# binaryClock.net
KiCad netlist of a schematic drawn in EAGLE
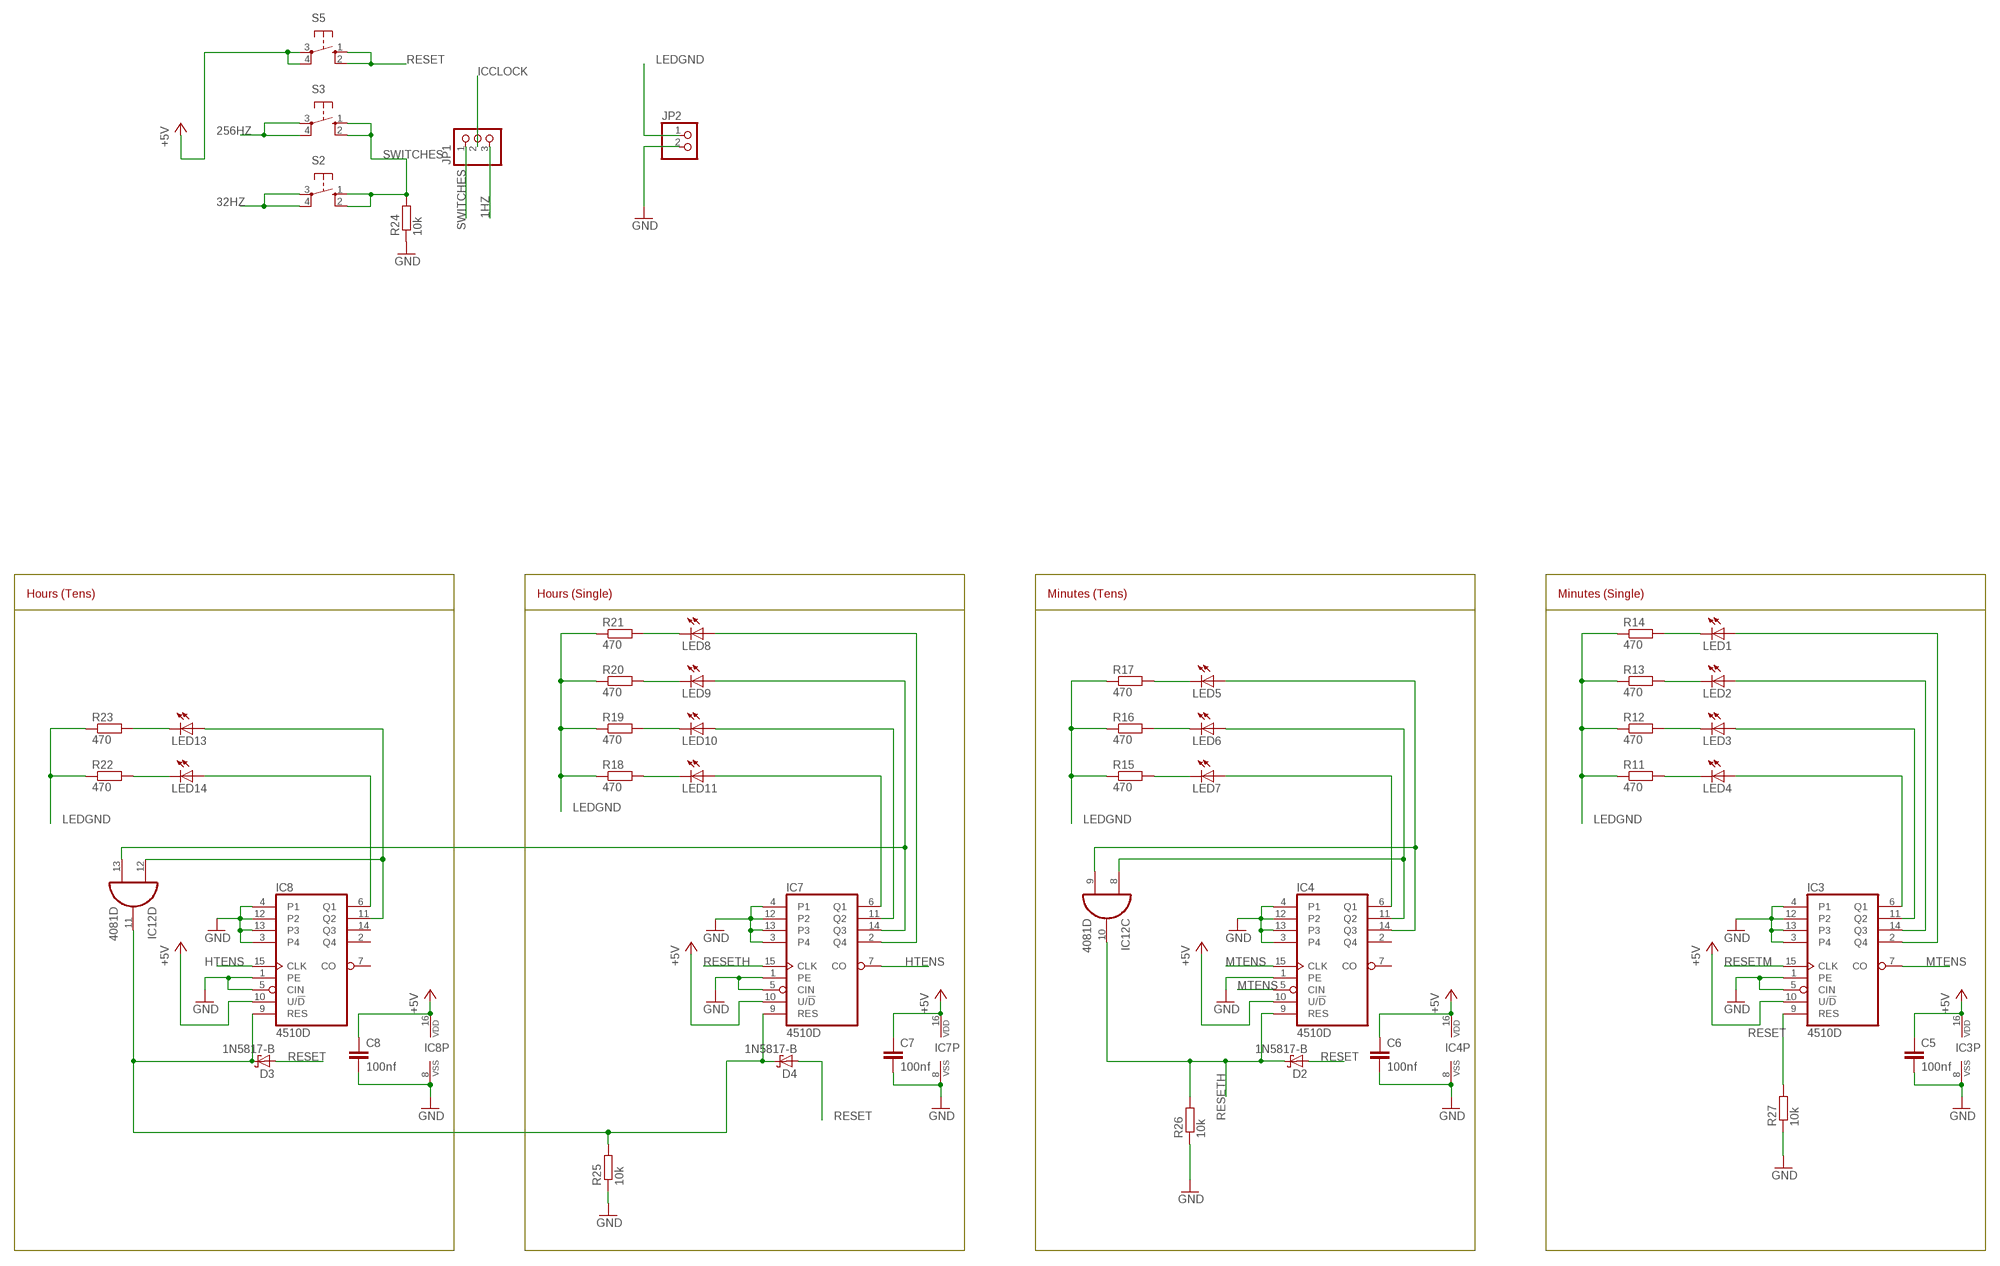
[diagram p0: schematic, sheet 1, part 1 of 2]
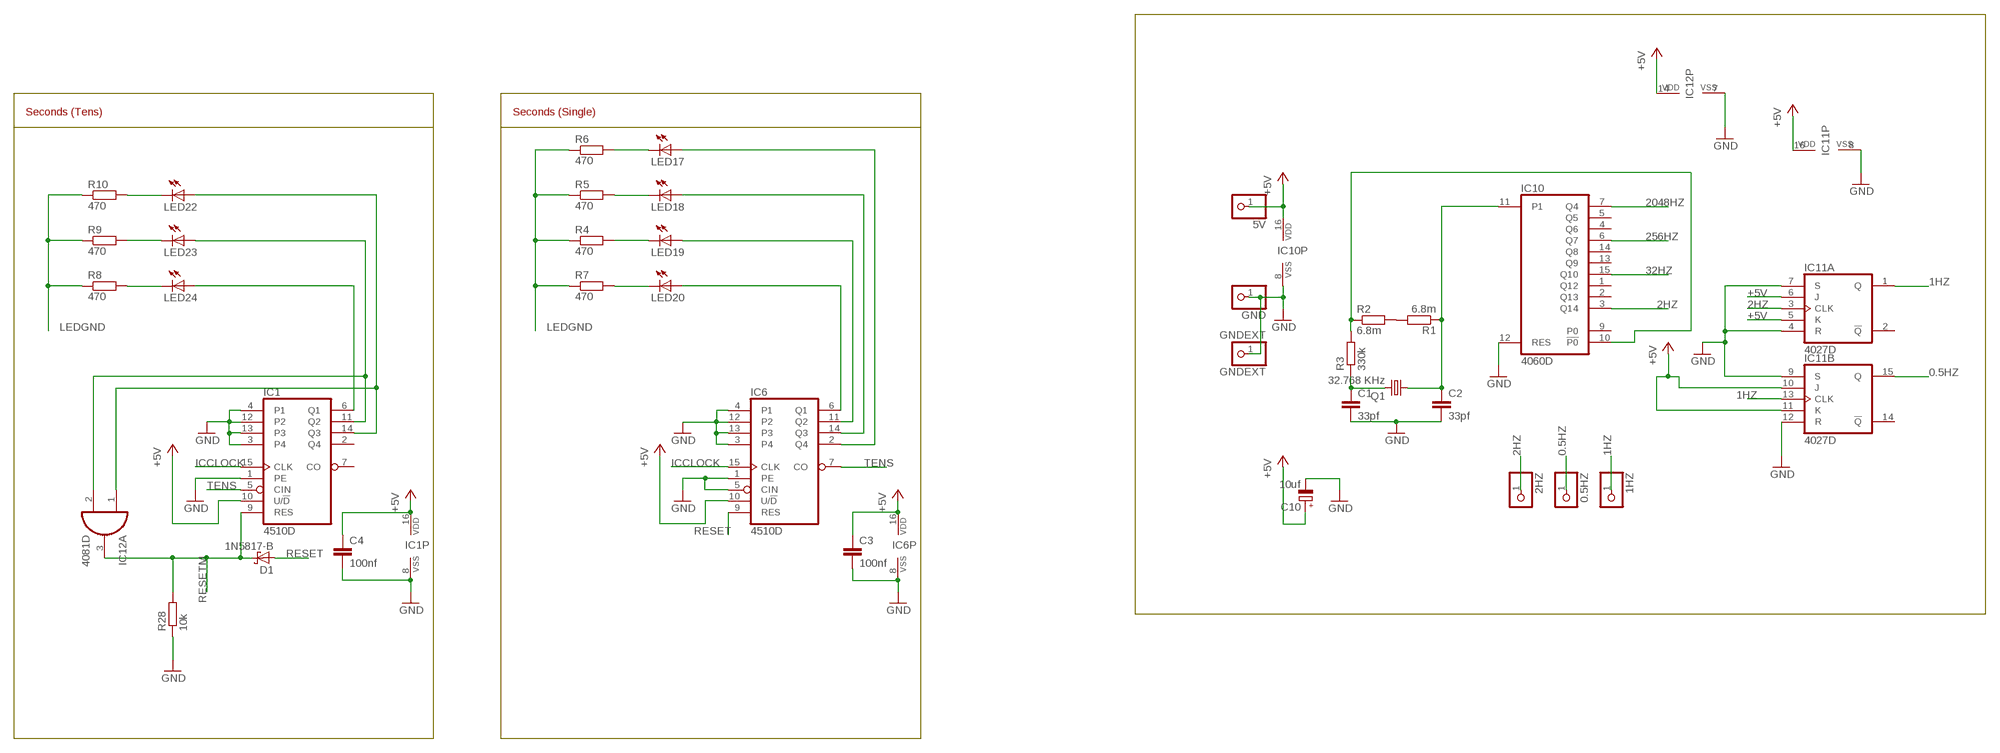
[diagram p1: schematic, sheet 1, part 2 of 2]

(export (version "E")
  (design (tool "Eeschema 10.0.6"))
  (components
    (comp (ref "0.5HZ")
      (value "PINHD-1X1")
      (footprint "eagle-import:1X01")
      (libsource (lib "eagle-import") (part "PINHD-1X1"))
    )
    (comp (ref "1HZ")
      (value "PINHD-1X1")
      (footprint "eagle-import:1X01")
      (libsource (lib "eagle-import") (part "PINHD-1X1"))
    )
    (comp (ref "2HZ")
      (value "PINHD-1X1")
      (footprint "eagle-import:1X01")
      (libsource (lib "eagle-import") (part "PINHD-1X1"))
    )
    (comp (ref "5V")
      (value "PINHD-1X1")
      (footprint "eagle-import:1X01")
      (libsource (lib "eagle-import") (part "PINHD-1X1"))
    )
    (comp (ref "C1")
      (value "33pf")
      (footprint "eagle-import:C025-030X050")
      (libsource (lib "eagle-import") (part "C-EU025-030X050"))
    )
    (comp (ref "C2")
      (value "33pf")
      (footprint "eagle-import:C025-030X050")
      (libsource (lib "eagle-import") (part "C-EU025-030X050"))
    )
    (comp (ref "C3")
      (value "100nf")
      (footprint "eagle-import:C025-030X050")
      (libsource (lib "eagle-import") (part "C-EU025-030X050"))
    )
    (comp (ref "C4")
      (value "100nf")
      (footprint "eagle-import:C025-030X050")
      (libsource (lib "eagle-import") (part "C-EU025-030X050"))
    )
    (comp (ref "C5")
      (value "100nf")
      (footprint "eagle-import:C025-030X050")
      (libsource (lib "eagle-import") (part "C-EU025-030X050"))
    )
    (comp (ref "C6")
      (value "100nf")
      (footprint "eagle-import:C025-030X050")
      (libsource (lib "eagle-import") (part "C-EU025-030X050"))
    )
    (comp (ref "C7")
      (value "100nf")
      (footprint "eagle-import:C025-030X050")
      (libsource (lib "eagle-import") (part "C-EU025-030X050"))
    )
    (comp (ref "C8")
      (value "100nf")
      (footprint "eagle-import:C025-030X050")
      (libsource (lib "eagle-import") (part "C-EU025-030X050"))
    )
    (comp (ref "C10")
      (value "10uf")
      (footprint "eagle-import:E2,5-5")
      (libsource (lib "eagle-import") (part "CPOL-EUE2.5-5"))
    )
    (comp (ref "D1")
      (value "1N5817-B")
      (footprint "eagle-import:DO41-7.6")
      (libsource (lib "eagle-import") (part "1N5817-B"))
    )
    (comp (ref "D2")
      (value "1N5817-B")
      (footprint "eagle-import:DO41-7.6")
      (libsource (lib "eagle-import") (part "1N5817-B"))
    )
    (comp (ref "D3")
      (value "1N5817-B")
      (footprint "eagle-import:DO41-7.6")
      (libsource (lib "eagle-import") (part "1N5817-B"))
    )
    (comp (ref "D4")
      (value "1N5817-B")
      (footprint "eagle-import:DO41-7.6")
      (libsource (lib "eagle-import") (part "1N5817-B"))
    )
    (comp (ref "GND")
      (value "PINHD-1X1")
      (footprint "eagle-import:1X01")
      (libsource (lib "eagle-import") (part "PINHD-1X1"))
    )
    (comp (ref "GNDEXT")
      (value "GNDEXT")
      (footprint "eagle-import:1X01")
      (libsource (lib "eagle-import") (part "PINHD-1X1"))
    )
    (comp (ref "IC1")
      (value "4510D")
      (footprint "eagle-import:SO16")
      (libsource (lib "eagle-import") (part "4510D"))
    )
    (comp (ref "IC3")
      (value "4510D")
      (footprint "eagle-import:SO16")
      (libsource (lib "eagle-import") (part "4510D"))
    )
    (comp (ref "IC4")
      (value "4510D")
      (footprint "eagle-import:SO16")
      (libsource (lib "eagle-import") (part "4510D"))
    )
    (comp (ref "IC6")
      (value "4510D")
      (footprint "eagle-import:SO16")
      (libsource (lib "eagle-import") (part "4510D"))
    )
    (comp (ref "IC7")
      (value "4510D")
      (footprint "eagle-import:SO16")
      (libsource (lib "eagle-import") (part "4510D"))
    )
    (comp (ref "IC8")
      (value "4510D")
      (footprint "eagle-import:SO16")
      (libsource (lib "eagle-import") (part "4510D"))
    )
    (comp (ref "IC10")
      (value "4060D")
      (footprint "eagle-import:SO16")
      (libsource (lib "eagle-import") (part "4060D"))
    )
    (comp (ref "IC11")
      (value "4027D")
      (footprint "eagle-import:SO16")
      (libsource (lib "eagle-import") (part "4027D"))
    )
    (comp (ref "IC12")
      (value "4081D")
      (footprint "eagle-import:SO14")
      (libsource (lib "eagle-import") (part "4081D"))
    )
    (comp (ref "JP1")
      (value "PINHD-1X3")
      (footprint "eagle-import:1X03")
      (libsource (lib "eagle-import") (part "PINHD-1X3"))
    )
    (comp (ref "JP2")
      (value "PINHD-1X2")
      (footprint "eagle-import:1X02")
      (libsource (lib "eagle-import") (part "PINHD-1X2"))
    )
    (comp (ref "LED1")
      (value "LED5MM")
      (footprint "eagle-import:LED5MM")
      (libsource (lib "eagle-import") (part "LED5MM"))
    )
    (comp (ref "LED2")
      (value "LED5MM")
      (footprint "eagle-import:LED5MM")
      (libsource (lib "eagle-import") (part "LED5MM"))
    )
    (comp (ref "LED3")
      (value "LED5MM")
      (footprint "eagle-import:LED5MM")
      (libsource (lib "eagle-import") (part "LED5MM"))
    )
    (comp (ref "LED4")
      (value "LED5MM")
      (footprint "eagle-import:LED5MM")
      (libsource (lib "eagle-import") (part "LED5MM"))
    )
    (comp (ref "LED5")
      (value "LED5MM")
      (footprint "eagle-import:LED5MM")
      (libsource (lib "eagle-import") (part "LED5MM"))
    )
    (comp (ref "LED6")
      (value "LED5MM")
      (footprint "eagle-import:LED5MM")
      (libsource (lib "eagle-import") (part "LED5MM"))
    )
    (comp (ref "LED7")
      (value "LED5MM")
      (footprint "eagle-import:LED5MM")
      (libsource (lib "eagle-import") (part "LED5MM"))
    )
    (comp (ref "LED8")
      (value "LED5MM")
      (footprint "eagle-import:LED5MM")
      (libsource (lib "eagle-import") (part "LED5MM"))
    )
    (comp (ref "LED9")
      (value "LED5MM")
      (footprint "eagle-import:LED5MM")
      (libsource (lib "eagle-import") (part "LED5MM"))
    )
    (comp (ref "LED10")
      (value "LED5MM")
      (footprint "eagle-import:LED5MM")
      (libsource (lib "eagle-import") (part "LED5MM"))
    )
    (comp (ref "LED11")
      (value "LED5MM")
      (footprint "eagle-import:LED5MM")
      (libsource (lib "eagle-import") (part "LED5MM"))
    )
    (comp (ref "LED13")
      (value "LED5MM")
      (footprint "eagle-import:LED5MM")
      (libsource (lib "eagle-import") (part "LED5MM"))
    )
    (comp (ref "LED14")
      (value "LED5MM")
      (footprint "eagle-import:LED5MM")
      (libsource (lib "eagle-import") (part "LED5MM"))
    )
    (comp (ref "LED17")
      (value "LED5MM")
      (footprint "eagle-import:LED5MM")
      (libsource (lib "eagle-import") (part "LED5MM"))
    )
    (comp (ref "LED18")
      (value "LED5MM")
      (footprint "eagle-import:LED5MM")
      (libsource (lib "eagle-import") (part "LED5MM"))
    )
    (comp (ref "LED19")
      (value "LED5MM")
      (footprint "eagle-import:LED5MM")
      (libsource (lib "eagle-import") (part "LED5MM"))
    )
    (comp (ref "LED20")
      (value "LED5MM")
      (footprint "eagle-import:LED5MM")
      (libsource (lib "eagle-import") (part "LED5MM"))
    )
    (comp (ref "LED22")
      (value "LED5MM")
      (footprint "eagle-import:LED5MM")
      (libsource (lib "eagle-import") (part "LED5MM"))
    )
    (comp (ref "LED23")
      (value "LED5MM")
      (footprint "eagle-import:LED5MM")
      (libsource (lib "eagle-import") (part "LED5MM"))
    )
    (comp (ref "LED24")
      (value "LED5MM")
      (footprint "eagle-import:LED5MM")
      (libsource (lib "eagle-import") (part "LED5MM"))
    )
    (comp (ref "Q1")
      (value "32.768 KHz")
      (footprint "eagle-import:TC26H")
      (libsource (lib "eagle-import") (part "CRYSTALTC26H"))
    )
    (comp (ref "R1")
      (value "6.8m")
      (footprint "eagle-import:R0805")
      (libsource (lib "eagle-import") (part "R-EU_R0805"))
    )
    (comp (ref "R2")
      (value "6.8m")
      (footprint "eagle-import:R0805")
      (libsource (lib "eagle-import") (part "R-EU_R0805"))
    )
    (comp (ref "R3")
      (value "330k")
      (footprint "eagle-import:R0805")
      (libsource (lib "eagle-import") (part "R-EU_R0805"))
    )
    (comp (ref "R4")
      (value "470")
      (footprint "eagle-import:R0805")
      (libsource (lib "eagle-import") (part "R-EU_R0805"))
    )
    (comp (ref "R5")
      (value "470")
      (footprint "eagle-import:R0805")
      (libsource (lib "eagle-import") (part "R-EU_R0805"))
    )
    (comp (ref "R6")
      (value "470")
      (footprint "eagle-import:R0805")
      (libsource (lib "eagle-import") (part "R-EU_R0805"))
    )
    (comp (ref "R7")
      (value "470")
      (footprint "eagle-import:R0805")
      (libsource (lib "eagle-import") (part "R-EU_R0805"))
    )
    (comp (ref "R8")
      (value "470")
      (footprint "eagle-import:R0805")
      (libsource (lib "eagle-import") (part "R-EU_R0805"))
    )
    (comp (ref "R9")
      (value "470")
      (footprint "eagle-import:R0805")
      (libsource (lib "eagle-import") (part "R-EU_R0805"))
    )
    (comp (ref "R10")
      (value "470")
      (footprint "eagle-import:R0805")
      (libsource (lib "eagle-import") (part "R-EU_R0805"))
    )
    (comp (ref "R11")
      (value "470")
      (footprint "eagle-import:R0805")
      (libsource (lib "eagle-import") (part "R-EU_R0805"))
    )
    (comp (ref "R12")
      (value "470")
      (footprint "eagle-import:R0805")
      (libsource (lib "eagle-import") (part "R-EU_R0805"))
    )
    (comp (ref "R13")
      (value "470")
      (footprint "eagle-import:R0805")
      (libsource (lib "eagle-import") (part "R-EU_R0805"))
    )
    (comp (ref "R14")
      (value "470")
      (footprint "eagle-import:R0805")
      (libsource (lib "eagle-import") (part "R-EU_R0805"))
    )
    (comp (ref "R15")
      (value "470")
      (footprint "eagle-import:R0805")
      (libsource (lib "eagle-import") (part "R-EU_R0805"))
    )
    (comp (ref "R16")
      (value "470")
      (footprint "eagle-import:R0805")
      (libsource (lib "eagle-import") (part "R-EU_R0805"))
    )
    (comp (ref "R17")
      (value "470")
      (footprint "eagle-import:R0805")
      (libsource (lib "eagle-import") (part "R-EU_R0805"))
    )
    (comp (ref "R18")
      (value "470")
      (footprint "eagle-import:R0805")
      (libsource (lib "eagle-import") (part "R-EU_R0805"))
    )
    (comp (ref "R19")
      (value "470")
      (footprint "eagle-import:R0805")
      (libsource (lib "eagle-import") (part "R-EU_R0805"))
    )
    (comp (ref "R20")
      (value "470")
      (footprint "eagle-import:R0805")
      (libsource (lib "eagle-import") (part "R-EU_R0805"))
    )
    (comp (ref "R21")
      (value "470")
      (footprint "eagle-import:R0805")
      (libsource (lib "eagle-import") (part "R-EU_R0805"))
    )
    (comp (ref "R22")
      (value "470")
      (footprint "eagle-import:R0805")
      (libsource (lib "eagle-import") (part "R-EU_R0805"))
    )
    (comp (ref "R23")
      (value "470")
      (footprint "eagle-import:R0805")
      (libsource (lib "eagle-import") (part "R-EU_R0805"))
    )
    (comp (ref "R24")
      (value "10k")
      (footprint "eagle-import:R0805")
      (libsource (lib "eagle-import") (part "R-EU_R0805"))
    )
    (comp (ref "R25")
      (value "10k")
      (footprint "eagle-import:R0805")
      (libsource (lib "eagle-import") (part "R-EU_R0805"))
    )
    (comp (ref "R26")
      (value "10k")
      (footprint "eagle-import:R0805")
      (libsource (lib "eagle-import") (part "R-EU_R0805"))
    )
    (comp (ref "R27")
      (value "10k")
      (footprint "eagle-import:R0805")
      (libsource (lib "eagle-import") (part "R-EU_R0805"))
    )
    (comp (ref "R28")
      (value "10k")
      (footprint "eagle-import:R0805")
      (libsource (lib "eagle-import") (part "R-EU_R0805"))
    )
    (comp (ref "S2")
      (value "10-XX")
      (footprint "eagle-import:B3F-10XX")
      (fields (field (name "MPN") "B3F-1000"))
      (libsource (lib "eagle-import") (part "10-XX"))
    )
    (comp (ref "S3")
      (value "10-XX")
      (footprint "eagle-import:B3F-10XX")
      (fields (field (name "MPN") "B3F-1000"))
      (libsource (lib "eagle-import") (part "10-XX"))
    )
    (comp (ref "S5")
      (value "10-XX")
      (footprint "eagle-import:B3F-10XX")
      (fields (field (name "MPN") "B3F-1000"))
      (libsource (lib "eagle-import") (part "10-XX"))
    )
  )
  (nets
    (net (code "1") (name "+5V") (class "Default")
      (node (ref "5V") (pin "1") (pinfunction "1_1") (pintype "passive"))
      (node (ref "C10") (pin "+") (pinfunction "+_+") (pintype "passive"))
      (node (ref "C3") (pin "1") (pinfunction "1_1") (pintype "passive"))
      (node (ref "C4") (pin "1") (pinfunction "1_1") (pintype "passive"))
      (node (ref "C5") (pin "1") (pinfunction "1_1") (pintype "passive"))
      (node (ref "C6") (pin "1") (pinfunction "1_1") (pintype "passive"))
      (node (ref "C7") (pin "1") (pinfunction "1_1") (pintype "passive"))
      (node (ref "C8") (pin "1") (pinfunction "1_1") (pintype "passive"))
      (node (ref "IC1") (pin "10") (pinfunction "U/~{D}_10") (pintype "input"))
      (node (ref "IC1") (pin "16") (pinfunction "VDD_16") (pintype "power_in"))
      (node (ref "IC10") (pin "16") (pinfunction "VDD_16") (pintype "power_in"))
      (node (ref "IC11") (pin "10") (pinfunction "J_10") (pintype "input"))
      (node (ref "IC11") (pin "11") (pinfunction "K_11") (pintype "input"))
      (node (ref "IC11") (pin "16") (pinfunction "VDD_16") (pintype "power_in"))
      (node (ref "IC11") (pin "5") (pinfunction "K_5") (pintype "input"))
      (node (ref "IC11") (pin "6") (pinfunction "J_6") (pintype "input"))
      (node (ref "IC12") (pin "14") (pinfunction "VDD_14") (pintype "power_in"))
      (node (ref "IC3") (pin "10") (pinfunction "U/~{D}_10") (pintype "input"))
      (node (ref "IC3") (pin "16") (pinfunction "VDD_16") (pintype "power_in"))
      (node (ref "IC4") (pin "10") (pinfunction "U/~{D}_10") (pintype "input"))
      (node (ref "IC4") (pin "16") (pinfunction "VDD_16") (pintype "power_in"))
      (node (ref "IC6") (pin "10") (pinfunction "U/~{D}_10") (pintype "input"))
      (node (ref "IC6") (pin "16") (pinfunction "VDD_16") (pintype "power_in"))
      (node (ref "IC7") (pin "10") (pinfunction "U/~{D}_10") (pintype "input"))
      (node (ref "IC7") (pin "16") (pinfunction "VDD_16") (pintype "power_in"))
      (node (ref "IC8") (pin "10") (pinfunction "U/~{D}_10") (pintype "input"))
      (node (ref "IC8") (pin "16") (pinfunction "VDD_16") (pintype "power_in"))
      (node (ref "S5") (pin "3") (pinfunction "P_3") (pintype "passive"))
      (node (ref "S5") (pin "4") (pinfunction "P1_4") (pintype "passive"))
    )
    (net (code "2") (name "/0.5HZ") (class "Default")
      (node (ref "0.5HZ") (pin "1") (pinfunction "1_1") (pintype "passive"))
      (node (ref "IC11") (pin "15") (pinfunction "Q_15") (pintype "output"))
    )
    (net (code "3") (name "/1HZ") (class "Default")
      (node (ref "1HZ") (pin "1") (pinfunction "1_1") (pintype "passive"))
      (node (ref "IC11") (pin "1") (pinfunction "Q_1") (pintype "output"))
      (node (ref "IC11") (pin "13") (pinfunction "CLK_13") (pintype "input"))
      (node (ref "JP1") (pin "3") (pinfunction "3_3") (pintype "passive"))
    )
    (net (code "4") (name "/2HZ") (class "Default")
      (node (ref "2HZ") (pin "1") (pinfunction "1_1") (pintype "passive"))
      (node (ref "IC10") (pin "3") (pinfunction "Q14_3") (pintype "output"))
      (node (ref "IC11") (pin "3") (pinfunction "CLK_3") (pintype "input"))
    )
    (net (code "5") (name "/32HZ") (class "Default")
      (node (ref "IC10") (pin "15") (pinfunction "Q10_15") (pintype "output"))
      (node (ref "S2") (pin "3") (pinfunction "P_3") (pintype "passive"))
      (node (ref "S2") (pin "4") (pinfunction "P1_4") (pintype "passive"))
    )
    (net (code "6") (name "/256HZ") (class "Default")
      (node (ref "IC10") (pin "6") (pinfunction "Q7_6") (pintype "output"))
      (node (ref "S3") (pin "3") (pinfunction "P_3") (pintype "passive"))
      (node (ref "S3") (pin "4") (pinfunction "P1_4") (pintype "passive"))
    )
    (net (code "7") (name "/2048HZ") (class "Default")
      (node (ref "IC10") (pin "7") (pinfunction "Q4_7") (pintype "output"))
    )
    (net (code "8") (name "/HTENS") (class "Default")
      (node (ref "IC7") (pin "7") (pinfunction "CO_7") (pintype "output"))
      (node (ref "IC8") (pin "15") (pinfunction "CLK_15") (pintype "input"))
    )
    (net (code "9") (name "/ICCLOCK") (class "Default")
      (node (ref "IC1") (pin "15") (pinfunction "CLK_15") (pintype "input"))
      (node (ref "IC6") (pin "15") (pinfunction "CLK_15") (pintype "input"))
      (node (ref "JP1") (pin "2") (pinfunction "2_2") (pintype "passive"))
    )
    (net (code "10") (name "/LEDGND") (class "Default")
      (node (ref "JP2") (pin "1") (pinfunction "1_1") (pintype "passive"))
      (node (ref "R10") (pin "1") (pinfunction "1_1") (pintype "passive"))
      (node (ref "R11") (pin "1") (pinfunction "1_1") (pintype "passive"))
      (node (ref "R12") (pin "1") (pinfunction "1_1") (pintype "passive"))
      (node (ref "R13") (pin "1") (pinfunction "1_1") (pintype "passive"))
      (node (ref "R14") (pin "1") (pinfunction "1_1") (pintype "passive"))
      (node (ref "R15") (pin "1") (pinfunction "1_1") (pintype "passive"))
      (node (ref "R16") (pin "1") (pinfunction "1_1") (pintype "passive"))
      (node (ref "R17") (pin "1") (pinfunction "1_1") (pintype "passive"))
      (node (ref "R18") (pin "1") (pinfunction "1_1") (pintype "passive"))
      (node (ref "R19") (pin "1") (pinfunction "1_1") (pintype "passive"))
      (node (ref "R20") (pin "1") (pinfunction "1_1") (pintype "passive"))
      (node (ref "R21") (pin "1") (pinfunction "1_1") (pintype "passive"))
      (node (ref "R22") (pin "1") (pinfunction "1_1") (pintype "passive"))
      (node (ref "R23") (pin "1") (pinfunction "1_1") (pintype "passive"))
      (node (ref "R4") (pin "1") (pinfunction "1_1") (pintype "passive"))
      (node (ref "R5") (pin "1") (pinfunction "1_1") (pintype "passive"))
      (node (ref "R6") (pin "1") (pinfunction "1_1") (pintype "passive"))
      (node (ref "R7") (pin "1") (pinfunction "1_1") (pintype "passive"))
      (node (ref "R8") (pin "1") (pinfunction "1_1") (pintype "passive"))
      (node (ref "R9") (pin "1") (pinfunction "1_1") (pintype "passive"))
    )
    (net (code "11") (name "/MTENS") (class "Default")
      (node (ref "IC3") (pin "7") (pinfunction "CO_7") (pintype "output"))
      (node (ref "IC4") (pin "15") (pinfunction "CLK_15") (pintype "input"))
      (node (ref "IC4") (pin "5") (pinfunction "CIN_5") (pintype "input"))
    )
    (net (code "12") (name "/RESET") (class "Default")
      (node (ref "D1") (pin "A") (pinfunction "A_A") (pintype "passive"))
      (node (ref "D2") (pin "A") (pinfunction "A_A") (pintype "passive"))
      (node (ref "D3") (pin "A") (pinfunction "A_A") (pintype "passive"))
      (node (ref "D4") (pin "A") (pinfunction "A_A") (pintype "passive"))
      (node (ref "IC3") (pin "9") (pinfunction "RES_9") (pintype "input"))
      (node (ref "IC6") (pin "9") (pinfunction "RES_9") (pintype "input"))
      (node (ref "R27") (pin "2") (pinfunction "2_2") (pintype "passive"))
      (node (ref "S5") (pin "1") (pinfunction "S_1") (pintype "passive"))
      (node (ref "S5") (pin "2") (pinfunction "S1_2") (pintype "passive"))
    )
    (net (code "13") (name "/RESETH") (class "Default")
      (node (ref "D2") (pin "C") (pinfunction "C_C") (pintype "passive"))
      (node (ref "IC12") (pin "10") (pinfunction "O_10") (pintype "output"))
      (node (ref "IC4") (pin "9") (pinfunction "RES_9") (pintype "input"))
      (node (ref "IC7") (pin "15") (pinfunction "CLK_15") (pintype "input"))
      (node (ref "R26") (pin "2") (pinfunction "2_2") (pintype "passive"))
    )
    (net (code "14") (name "/RESETM") (class "Default")
      (node (ref "D1") (pin "C") (pinfunction "C_C") (pintype "passive"))
      (node (ref "IC1") (pin "9") (pinfunction "RES_9") (pintype "input"))
      (node (ref "IC12") (pin "3") (pinfunction "O_3") (pintype "output"))
      (node (ref "IC3") (pin "15") (pinfunction "CLK_15") (pintype "input"))
      (node (ref "R28") (pin "2") (pinfunction "2_2") (pintype "passive"))
    )
    (net (code "15") (name "/SWITCHES") (class "Default")
      (node (ref "JP1") (pin "1") (pinfunction "1_1") (pintype "passive"))
      (node (ref "R24") (pin "2") (pinfunction "2_2") (pintype "passive"))
      (node (ref "S2") (pin "1") (pinfunction "S_1") (pintype "passive"))
      (node (ref "S2") (pin "2") (pinfunction "S1_2") (pintype "passive"))
      (node (ref "S3") (pin "1") (pinfunction "S_1") (pintype "passive"))
      (node (ref "S3") (pin "2") (pinfunction "S1_2") (pintype "passive"))
    )
    (net (code "16") (name "/TENS") (class "Default")
      (node (ref "IC1") (pin "5") (pinfunction "CIN_5") (pintype "input"))
      (node (ref "IC6") (pin "7") (pinfunction "CO_7") (pintype "output"))
    )
    (net (code "17") (name "GND") (class "Default")
      (node (ref "C1") (pin "2") (pinfunction "2_2") (pintype "passive"))
      (node (ref "C10") (pin "-") (pinfunction "-_-") (pintype "passive"))
      (node (ref "C2") (pin "2") (pinfunction "2_2") (pintype "passive"))
      (node (ref "C3") (pin "2") (pinfunction "2_2") (pintype "passive"))
      (node (ref "C4") (pin "2") (pinfunction "2_2") (pintype "passive"))
      (node (ref "C5") (pin "2") (pinfunction "2_2") (pintype "passive"))
      (node (ref "C6") (pin "2") (pinfunction "2_2") (pintype "passive"))
      (node (ref "C7") (pin "2") (pinfunction "2_2") (pintype "passive"))
      (node (ref "C8") (pin "2") (pinfunction "2_2") (pintype "passive"))
      (node (ref "GND") (pin "1") (pinfunction "1_1") (pintype "passive"))
      (node (ref "GNDEXT") (pin "1") (pinfunction "1_1") (pintype "passive"))
      (node (ref "IC1") (pin "1") (pinfunction "PE_1") (pintype "input"))
      (node (ref "IC1") (pin "12") (pinfunction "P2_12") (pintype "input"))
      (node (ref "IC1") (pin "13") (pinfunction "P3_13") (pintype "input"))
      (node (ref "IC1") (pin "3") (pinfunction "P4_3") (pintype "input"))
      (node (ref "IC1") (pin "4") (pinfunction "P1_4") (pintype "input"))
      (node (ref "IC1") (pin "8") (pinfunction "VSS_8") (pintype "power_in"))
      (node (ref "IC10") (pin "12") (pinfunction "RES_12") (pintype "input"))
      (node (ref "IC10") (pin "8") (pinfunction "VSS_8") (pintype "power_in"))
      (node (ref "IC11") (pin "12") (pinfunction "R_12") (pintype "input"))
      (node (ref "IC11") (pin "4") (pinfunction "R_4") (pintype "input"))
      (node (ref "IC11") (pin "7") (pinfunction "S_7") (pintype "input"))
      (node (ref "IC11") (pin "8") (pinfunction "VSS_8") (pintype "power_in"))
      (node (ref "IC11") (pin "9") (pinfunction "S_9") (pintype "input"))
      (node (ref "IC12") (pin "7") (pinfunction "VSS_7") (pintype "power_in"))
      (node (ref "IC3") (pin "1") (pinfunction "PE_1") (pintype "input"))
      (node (ref "IC3") (pin "12") (pinfunction "P2_12") (pintype "input"))
      (node (ref "IC3") (pin "13") (pinfunction "P3_13") (pintype "input"))
      (node (ref "IC3") (pin "3") (pinfunction "P4_3") (pintype "input"))
      (node (ref "IC3") (pin "4") (pinfunction "P1_4") (pintype "input"))
      (node (ref "IC3") (pin "5") (pinfunction "CIN_5") (pintype "input"))
      (node (ref "IC3") (pin "8") (pinfunction "VSS_8") (pintype "power_in"))
      (node (ref "IC4") (pin "1") (pinfunction "PE_1") (pintype "input"))
      (node (ref "IC4") (pin "12") (pinfunction "P2_12") (pintype "input"))
      (node (ref "IC4") (pin "13") (pinfunction "P3_13") (pintype "input"))
      (node (ref "IC4") (pin "3") (pinfunction "P4_3") (pintype "input"))
      (node (ref "IC4") (pin "4") (pinfunction "P1_4") (pintype "input"))
      (node (ref "IC4") (pin "8") (pinfunction "VSS_8") (pintype "power_in"))
      (node (ref "IC6") (pin "1") (pinfunction "PE_1") (pintype "input"))
      (node (ref "IC6") (pin "12") (pinfunction "P2_12") (pintype "input"))
      (node (ref "IC6") (pin "13") (pinfunction "P3_13") (pintype "input"))
      (node (ref "IC6") (pin "3") (pinfunction "P4_3") (pintype "input"))
      (node (ref "IC6") (pin "4") (pinfunction "P1_4") (pintype "input"))
      (node (ref "IC6") (pin "5") (pinfunction "CIN_5") (pintype "input"))
      (node (ref "IC6") (pin "8") (pinfunction "VSS_8") (pintype "power_in"))
      (node (ref "IC7") (pin "1") (pinfunction "PE_1") (pintype "input"))
      (node (ref "IC7") (pin "12") (pinfunction "P2_12") (pintype "input"))
      (node (ref "IC7") (pin "13") (pinfunction "P3_13") (pintype "input"))
      (node (ref "IC7") (pin "3") (pinfunction "P4_3") (pintype "input"))
      (node (ref "IC7") (pin "4") (pinfunction "P1_4") (pintype "input"))
      (node (ref "IC7") (pin "5") (pinfunction "CIN_5") (pintype "input"))
      (node (ref "IC7") (pin "8") (pinfunction "VSS_8") (pintype "power_in"))
      (node (ref "IC8") (pin "1") (pinfunction "PE_1") (pintype "input"))
      (node (ref "IC8") (pin "12") (pinfunction "P2_12") (pintype "input"))
      (node (ref "IC8") (pin "13") (pinfunction "P3_13") (pintype "input"))
      (node (ref "IC8") (pin "3") (pinfunction "P4_3") (pintype "input"))
      (node (ref "IC8") (pin "4") (pinfunction "P1_4") (pintype "input"))
      (node (ref "IC8") (pin "5") (pinfunction "CIN_5") (pintype "input"))
      (node (ref "IC8") (pin "8") (pinfunction "VSS_8") (pintype "power_in"))
      (node (ref "JP2") (pin "2") (pinfunction "2_2") (pintype "passive"))
      (node (ref "R24") (pin "1") (pinfunction "1_1") (pintype "passive"))
      (node (ref "R25") (pin "1") (pinfunction "1_1") (pintype "passive"))
      (node (ref "R26") (pin "1") (pinfunction "1_1") (pintype "passive"))
      (node (ref "R27") (pin "1") (pinfunction "1_1") (pintype "passive"))
      (node (ref "R28") (pin "1") (pinfunction "1_1") (pintype "passive"))
    )
    (net (code "18") (name "Net-(C1-Pad1)") (class "Default")
      (node (ref "C1") (pin "1") (pinfunction "1_1") (pintype "passive"))
      (node (ref "Q1") (pin "2") (pinfunction "2_2") (pintype "passive"))
      (node (ref "R3") (pin "1") (pinfunction "1_1") (pintype "passive"))
    )
    (net (code "19") (name "Net-(IC1A-Q1)") (class "Default")
      (node (ref "IC1") (pin "6") (pinfunction "Q1_6") (pintype "output"))
      (node (ref "LED24") (pin "A") (pinfunction "A_A") (pintype "passive"))
    )
    (net (code "20") (name "Net-(IC3A-Q1)") (class "Default")
      (node (ref "IC3") (pin "6") (pinfunction "Q1_6") (pintype "output"))
      (node (ref "LED4") (pin "A") (pinfunction "A_A") (pintype "passive"))
    )
    (net (code "21") (name "Net-(IC3A-Q2)") (class "Default")
      (node (ref "IC3") (pin "11") (pinfunction "Q2_11") (pintype "output"))
      (node (ref "LED3") (pin "A") (pinfunction "A_A") (pintype "passive"))
    )
    (net (code "22") (name "Net-(IC3A-Q3)") (class "Default")
      (node (ref "IC3") (pin "14") (pinfunction "Q3_14") (pintype "output"))
      (node (ref "LED2") (pin "A") (pinfunction "A_A") (pintype "passive"))
    )
    (net (code "23") (name "Net-(IC3A-Q4)") (class "Default")
      (node (ref "IC3") (pin "2") (pinfunction "Q4_2") (pintype "output"))
      (node (ref "LED1") (pin "A") (pinfunction "A_A") (pintype "passive"))
    )
    (net (code "24") (name "Net-(IC4A-Q1)") (class "Default")
      (node (ref "IC4") (pin "6") (pinfunction "Q1_6") (pintype "output"))
      (node (ref "LED7") (pin "A") (pinfunction "A_A") (pintype "passive"))
    )
    (net (code "25") (name "Net-(IC6A-Q1)") (class "Default")
      (node (ref "IC6") (pin "6") (pinfunction "Q1_6") (pintype "output"))
      (node (ref "LED20") (pin "A") (pinfunction "A_A") (pintype "passive"))
    )
    (net (code "26") (name "Net-(IC6A-Q2)") (class "Default")
      (node (ref "IC6") (pin "11") (pinfunction "Q2_11") (pintype "output"))
      (node (ref "LED19") (pin "A") (pinfunction "A_A") (pintype "passive"))
    )
    (net (code "27") (name "Net-(IC6A-Q3)") (class "Default")
      (node (ref "IC6") (pin "14") (pinfunction "Q3_14") (pintype "output"))
      (node (ref "LED18") (pin "A") (pinfunction "A_A") (pintype "passive"))
    )
    (net (code "28") (name "Net-(IC6A-Q4)") (class "Default")
      (node (ref "IC6") (pin "2") (pinfunction "Q4_2") (pintype "output"))
      (node (ref "LED17") (pin "A") (pinfunction "A_A") (pintype "passive"))
    )
    (net (code "29") (name "Net-(IC7A-Q1)") (class "Default")
      (node (ref "IC7") (pin "6") (pinfunction "Q1_6") (pintype "output"))
      (node (ref "LED11") (pin "A") (pinfunction "A_A") (pintype "passive"))
    )
    (net (code "30") (name "Net-(IC7A-Q2)") (class "Default")
      (node (ref "IC7") (pin "11") (pinfunction "Q2_11") (pintype "output"))
      (node (ref "LED10") (pin "A") (pinfunction "A_A") (pintype "passive"))
    )
    (net (code "31") (name "Net-(IC7A-Q4)") (class "Default")
      (node (ref "IC7") (pin "2") (pinfunction "Q4_2") (pintype "output"))
      (node (ref "LED8") (pin "A") (pinfunction "A_A") (pintype "passive"))
    )
    (net (code "32") (name "Net-(IC8A-Q1)") (class "Default")
      (node (ref "IC8") (pin "6") (pinfunction "Q1_6") (pintype "output"))
      (node (ref "LED14") (pin "A") (pinfunction "A_A") (pintype "passive"))
    )
    (net (code "33") (name "Net-(IC10A-P1)") (class "Default")
      (node (ref "C2") (pin "1") (pinfunction "1_1") (pintype "passive"))
      (node (ref "IC10") (pin "11") (pinfunction "P1_11") (pintype "input"))
      (node (ref "Q1") (pin "1") (pinfunction "1_1") (pintype "passive"))
      (node (ref "R1") (pin "1") (pinfunction "1_1") (pintype "passive"))
    )
    (net (code "34") (name "Net-(IC10A-~{P0})") (class "Default")
      (node (ref "IC10") (pin "10") (pinfunction "~{P0}_10") (pintype "output"))
      (node (ref "R2") (pin "1") (pinfunction "1_1") (pintype "passive"))
      (node (ref "R3") (pin "2") (pinfunction "2_2") (pintype "passive"))
    )
    (net (code "35") (name "Net-(IC12A-I0)") (class "Default")
      (node (ref "IC1") (pin "14") (pinfunction "Q3_14") (pintype "output"))
      (node (ref "IC12") (pin "1") (pinfunction "I0_1") (pintype "input"))
      (node (ref "LED22") (pin "A") (pinfunction "A_A") (pintype "passive"))
    )
    (net (code "36") (name "Net-(IC12A-I1)") (class "Default")
      (node (ref "IC1") (pin "11") (pinfunction "Q2_11") (pintype "output"))
      (node (ref "IC12") (pin "2") (pinfunction "I1_2") (pintype "input"))
      (node (ref "LED23") (pin "A") (pinfunction "A_A") (pintype "passive"))
    )
    (net (code "37") (name "Net-(IC12C-I0)") (class "Default")
      (node (ref "IC12") (pin "8") (pinfunction "I0_8") (pintype "input"))
      (node (ref "IC4") (pin "11") (pinfunction "Q2_11") (pintype "output"))
      (node (ref "LED6") (pin "A") (pinfunction "A_A") (pintype "passive"))
    )
    (net (code "38") (name "Net-(IC12C-I1)") (class "Default")
      (node (ref "IC12") (pin "9") (pinfunction "I1_9") (pintype "input"))
      (node (ref "IC4") (pin "14") (pinfunction "Q3_14") (pintype "output"))
      (node (ref "LED5") (pin "A") (pinfunction "A_A") (pintype "passive"))
    )
    (net (code "39") (name "Net-(IC12D-I0)") (class "Default")
      (node (ref "IC12") (pin "12") (pinfunction "I0_12") (pintype "input"))
      (node (ref "IC8") (pin "11") (pinfunction "Q2_11") (pintype "output"))
      (node (ref "LED13") (pin "A") (pinfunction "A_A") (pintype "passive"))
    )
    (net (code "40") (name "Net-(IC12D-I1)") (class "Default")
      (node (ref "IC12") (pin "13") (pinfunction "I1_13") (pintype "input"))
      (node (ref "IC7") (pin "14") (pinfunction "Q3_14") (pintype "output"))
      (node (ref "LED9") (pin "A") (pinfunction "A_A") (pintype "passive"))
    )
    (net (code "41") (name "Net-(IC12D-O)") (class "Default")
      (node (ref "D3") (pin "C") (pinfunction "C_C") (pintype "passive"))
      (node (ref "D4") (pin "C") (pinfunction "C_C") (pintype "passive"))
      (node (ref "IC12") (pin "11") (pinfunction "O_11") (pintype "output"))
      (node (ref "IC7") (pin "9") (pinfunction "RES_9") (pintype "input"))
      (node (ref "IC8") (pin "9") (pinfunction "RES_9") (pintype "input"))
      (node (ref "R25") (pin "2") (pinfunction "2_2") (pintype "passive"))
    )
    (net (code "42") (name "Net-(LED1-C)") (class "Default")
      (node (ref "LED1") (pin "K") (pinfunction "C_K") (pintype "passive"))
      (node (ref "R14") (pin "2") (pinfunction "2_2") (pintype "passive"))
    )
    (net (code "43") (name "Net-(LED2-C)") (class "Default")
      (node (ref "LED2") (pin "K") (pinfunction "C_K") (pintype "passive"))
      (node (ref "R13") (pin "2") (pinfunction "2_2") (pintype "passive"))
    )
    (net (code "44") (name "Net-(LED3-C)") (class "Default")
      (node (ref "LED3") (pin "K") (pinfunction "C_K") (pintype "passive"))
      (node (ref "R12") (pin "2") (pinfunction "2_2") (pintype "passive"))
    )
    (net (code "45") (name "Net-(LED4-C)") (class "Default")
      (node (ref "LED4") (pin "K") (pinfunction "C_K") (pintype "passive"))
      (node (ref "R11") (pin "2") (pinfunction "2_2") (pintype "passive"))
    )
    (net (code "46") (name "Net-(LED5-C)") (class "Default")
      (node (ref "LED5") (pin "K") (pinfunction "C_K") (pintype "passive"))
      (node (ref "R17") (pin "2") (pinfunction "2_2") (pintype "passive"))
    )
    (net (code "47") (name "Net-(LED6-C)") (class "Default")
      (node (ref "LED6") (pin "K") (pinfunction "C_K") (pintype "passive"))
      (node (ref "R16") (pin "2") (pinfunction "2_2") (pintype "passive"))
    )
    (net (code "48") (name "Net-(LED7-C)") (class "Default")
      (node (ref "LED7") (pin "K") (pinfunction "C_K") (pintype "passive"))
      (node (ref "R15") (pin "2") (pinfunction "2_2") (pintype "passive"))
    )
    (net (code "49") (name "Net-(LED8-C)") (class "Default")
      (node (ref "LED8") (pin "K") (pinfunction "C_K") (pintype "passive"))
      (node (ref "R21") (pin "2") (pinfunction "2_2") (pintype "passive"))
    )
    (net (code "50") (name "Net-(LED9-C)") (class "Default")
      (node (ref "LED9") (pin "K") (pinfunction "C_K") (pintype "passive"))
      (node (ref "R20") (pin "2") (pinfunction "2_2") (pintype "passive"))
    )
    (net (code "51") (name "Net-(LED10-C)") (class "Default")
      (node (ref "LED10") (pin "K") (pinfunction "C_K") (pintype "passive"))
      (node (ref "R19") (pin "2") (pinfunction "2_2") (pintype "passive"))
    )
    (net (code "52") (name "Net-(LED11-C)") (class "Default")
      (node (ref "LED11") (pin "K") (pinfunction "C_K") (pintype "passive"))
      (node (ref "R18") (pin "2") (pinfunction "2_2") (pintype "passive"))
    )
    (net (code "53") (name "Net-(LED13-C)") (class "Default")
      (node (ref "LED13") (pin "K") (pinfunction "C_K") (pintype "passive"))
      (node (ref "R23") (pin "2") (pinfunction "2_2") (pintype "passive"))
    )
    (net (code "54") (name "Net-(LED14-C)") (class "Default")
      (node (ref "LED14") (pin "K") (pinfunction "C_K") (pintype "passive"))
      (node (ref "R22") (pin "2") (pinfunction "2_2") (pintype "passive"))
    )
    (net (code "55") (name "Net-(LED17-C)") (class "Default")
      (node (ref "LED17") (pin "K") (pinfunction "C_K") (pintype "passive"))
      (node (ref "R6") (pin "2") (pinfunction "2_2") (pintype "passive"))
    )
    (net (code "56") (name "Net-(LED18-C)") (class "Default")
      (node (ref "LED18") (pin "K") (pinfunction "C_K") (pintype "passive"))
      (node (ref "R5") (pin "2") (pinfunction "2_2") (pintype "passive"))
    )
    (net (code "57") (name "Net-(LED19-C)") (class "Default")
      (node (ref "LED19") (pin "K") (pinfunction "C_K") (pintype "passive"))
      (node (ref "R4") (pin "2") (pinfunction "2_2") (pintype "passive"))
    )
    (net (code "58") (name "Net-(LED20-C)") (class "Default")
      (node (ref "LED20") (pin "K") (pinfunction "C_K") (pintype "passive"))
      (node (ref "R7") (pin "2") (pinfunction "2_2") (pintype "passive"))
    )
    (net (code "59") (name "Net-(LED22-C)") (class "Default")
      (node (ref "LED22") (pin "K") (pinfunction "C_K") (pintype "passive"))
      (node (ref "R10") (pin "2") (pinfunction "2_2") (pintype "passive"))
    )
    (net (code "60") (name "Net-(LED23-C)") (class "Default")
      (node (ref "LED23") (pin "K") (pinfunction "C_K") (pintype "passive"))
      (node (ref "R9") (pin "2") (pinfunction "2_2") (pintype "passive"))
    )
    (net (code "61") (name "Net-(LED24-C)") (class "Default")
      (node (ref "LED24") (pin "K") (pinfunction "C_K") (pintype "passive"))
      (node (ref "R8") (pin "2") (pinfunction "2_2") (pintype "passive"))
    )
    (net (code "62") (name "Net-(R1-Pad2)") (class "Default")
      (node (ref "R1") (pin "2") (pinfunction "2_2") (pintype "passive"))
      (node (ref "R2") (pin "2") (pinfunction "2_2") (pintype "passive"))
    )
    (net (code "63") (name "unconnected-(IC1A-CO-Pad7)") (class "Default")
      (node (ref "IC1") (pin "7") (pinfunction "CO_7") (pintype "output"))
    )
    (net (code "64") (name "unconnected-(IC1A-Q4-Pad2)") (class "Default")
      (node (ref "IC1") (pin "2") (pinfunction "Q4_2") (pintype "output"))
    )
    (net (code "65") (name "unconnected-(IC4A-CO-Pad7)") (class "Default")
      (node (ref "IC4") (pin "7") (pinfunction "CO_7") (pintype "output"))
    )
    (net (code "66") (name "unconnected-(IC4A-Q4-Pad2)") (class "Default")
      (node (ref "IC4") (pin "2") (pinfunction "Q4_2") (pintype "output"))
    )
    (net (code "67") (name "unconnected-(IC8A-CO-Pad7)") (class "Default")
      (node (ref "IC8") (pin "7") (pinfunction "CO_7") (pintype "output"))
    )
    (net (code "68") (name "unconnected-(IC8A-Q3-Pad14)") (class "Default")
      (node (ref "IC8") (pin "14") (pinfunction "Q3_14") (pintype "output"))
    )
    (net (code "69") (name "unconnected-(IC8A-Q4-Pad2)") (class "Default")
      (node (ref "IC8") (pin "2") (pinfunction "Q4_2") (pintype "output"))
    )
    (net (code "70") (name "unconnected-(IC10A-P0-Pad9)") (class "Default")
      (node (ref "IC10") (pin "9") (pinfunction "P0_9") (pintype "output"))
    )
    (net (code "71") (name "unconnected-(IC10A-Q5-Pad5)") (class "Default")
      (node (ref "IC10") (pin "5") (pinfunction "Q5_5") (pintype "output"))
    )
    (net (code "72") (name "unconnected-(IC10A-Q6-Pad4)") (class "Default")
      (node (ref "IC10") (pin "4") (pinfunction "Q6_4") (pintype "output"))
    )
    (net (code "73") (name "unconnected-(IC10A-Q8-Pad14)") (class "Default")
      (node (ref "IC10") (pin "14") (pinfunction "Q8_14") (pintype "output"))
    )
    (net (code "74") (name "unconnected-(IC10A-Q9-Pad13)") (class "Default")
      (node (ref "IC10") (pin "13") (pinfunction "Q9_13") (pintype "output"))
    )
    (net (code "75") (name "unconnected-(IC10A-Q12-Pad1)") (class "Default")
      (node (ref "IC10") (pin "1") (pinfunction "Q12_1") (pintype "output"))
    )
    (net (code "76") (name "unconnected-(IC10A-Q13-Pad2)") (class "Default")
      (node (ref "IC10") (pin "2") (pinfunction "Q13_2") (pintype "output"))
    )
    (net (code "77") (name "unconnected-(IC11A-~{Q}-Pad2)") (class "Default")
      (node (ref "IC11") (pin "2") (pinfunction "~{Q}_2") (pintype "output"))
    )
    (net (code "78") (name "unconnected-(IC11B-~{Q}-Pad14)") (class "Default")
      (node (ref "IC11") (pin "14") (pinfunction "~{Q}_14") (pintype "output"))
    )
  )
)
